# Peripherals.net
KiCad netlist of a schematic drawn in Altium Designer
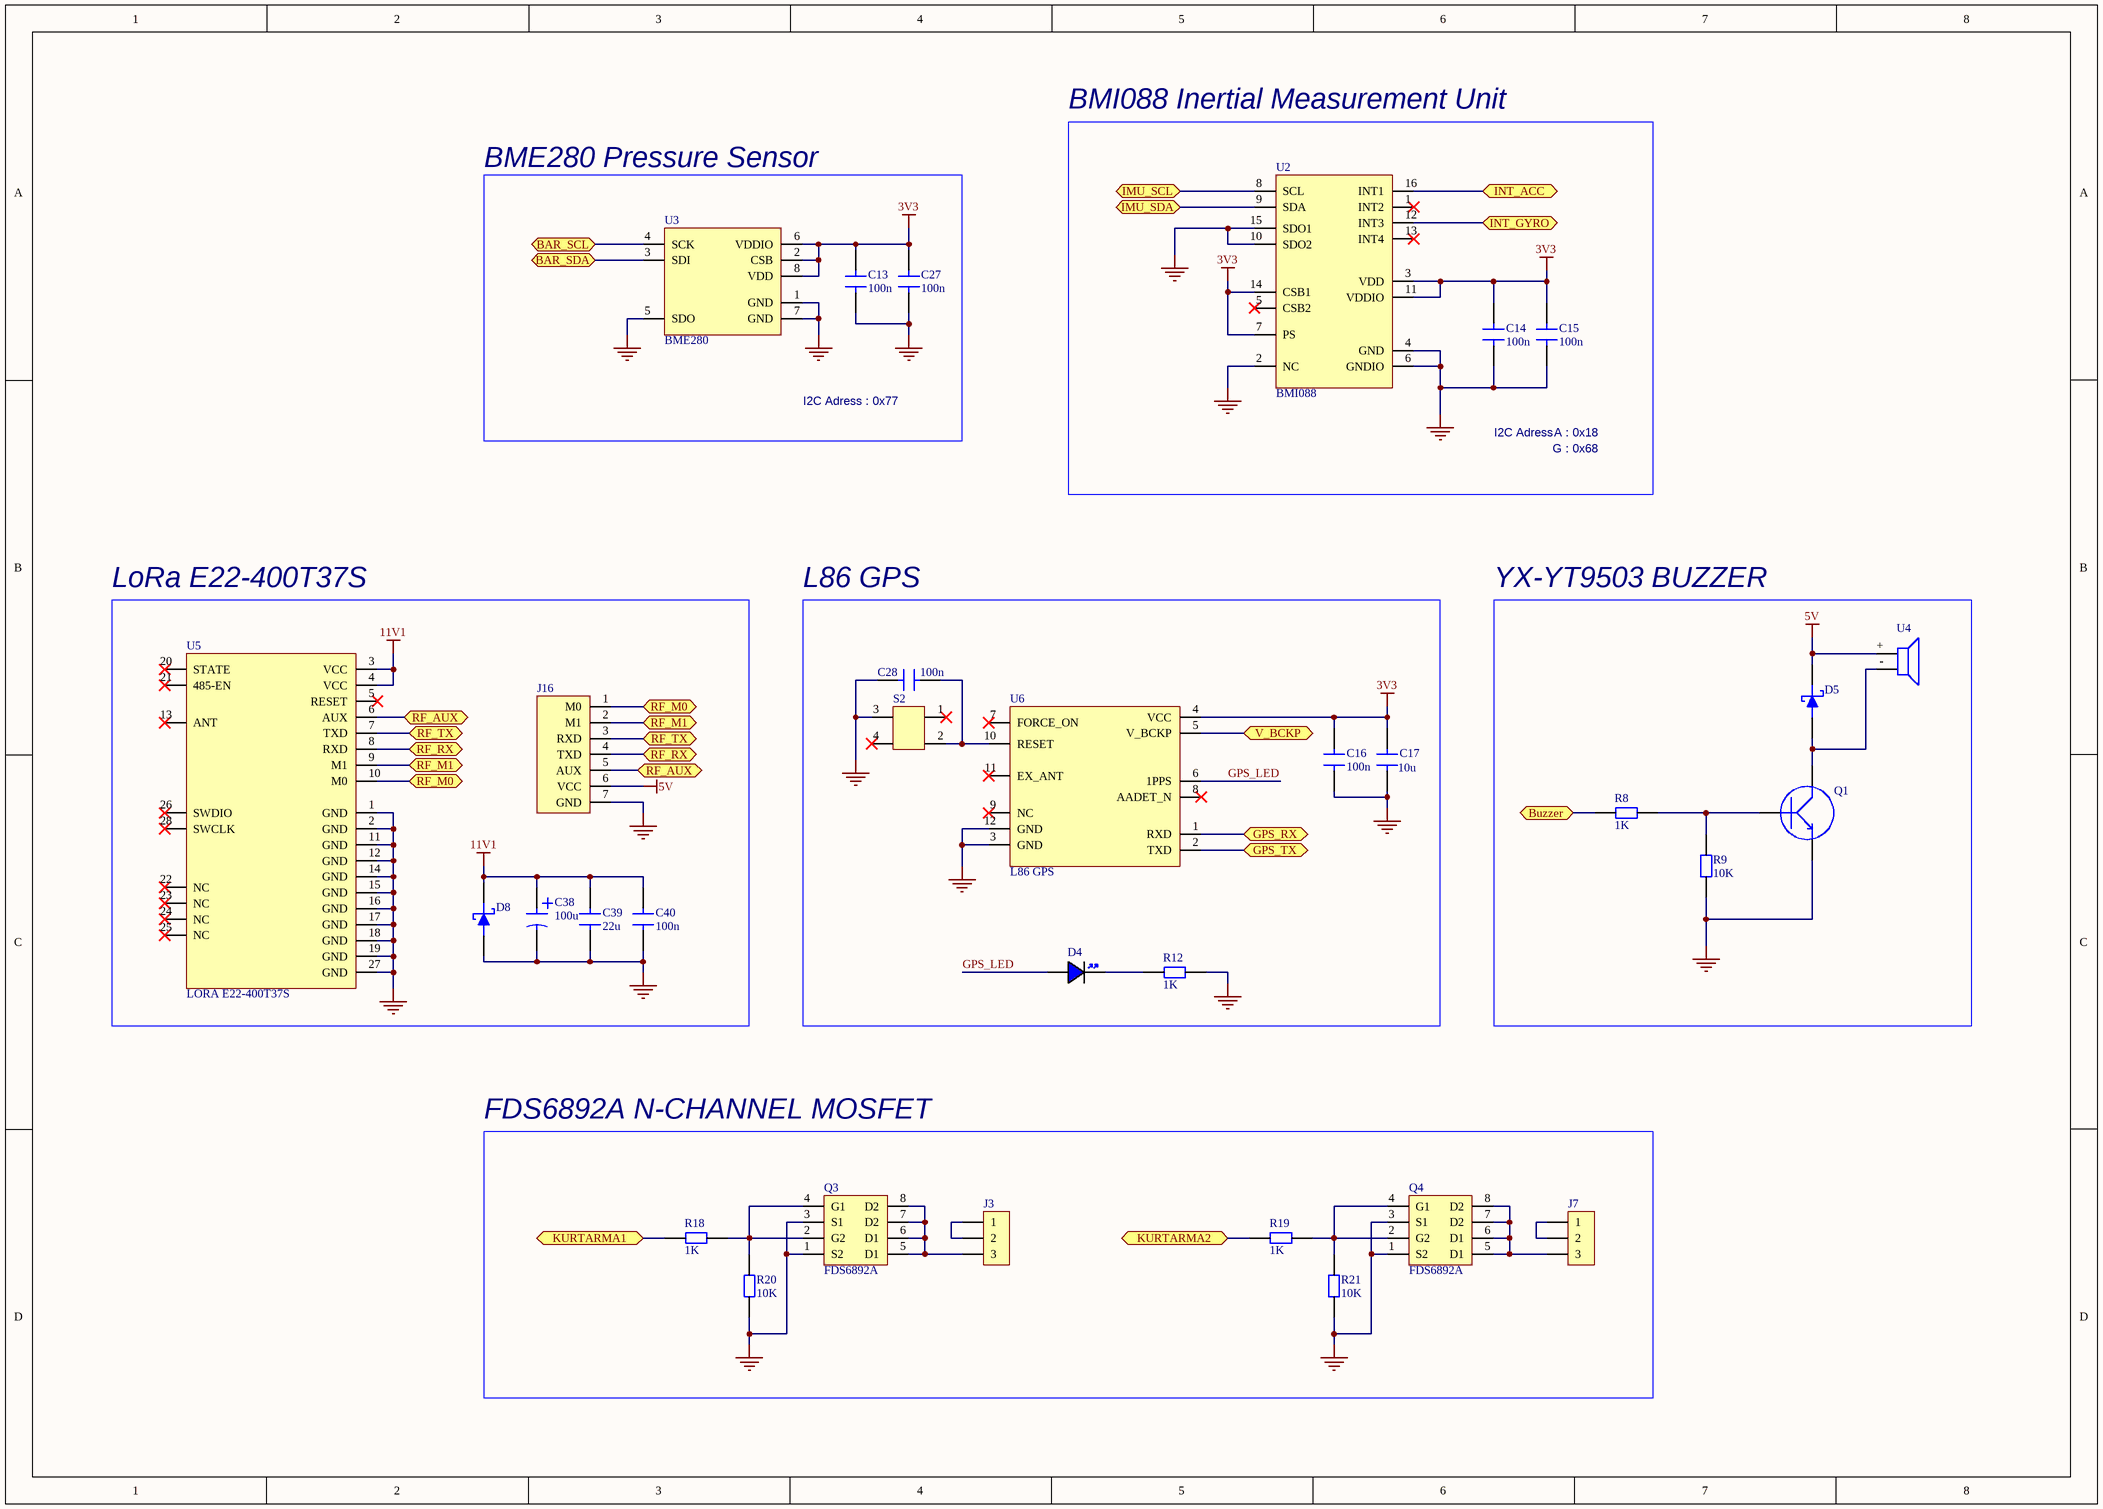
[diagram p0: Peripherals.SchDoc]

(export (version "E")
  (design (tool "Eeschema 10.0.6"))
  (components
    (comp (ref "C13")
      (value "100n")
      (footprint "CAP 0603")
      (description "Capacitor SMD 0603 50V")
      (libsource (lib "Schlib") (part "CAP 0603 50V"))
    )
    (comp (ref "C14")
      (value "100n")
      (footprint "CAP 0603")
      (description "Capacitor SMD 0603 50V")
      (libsource (lib "Schlib") (part "CAP 0603 50V"))
    )
    (comp (ref "C15")
      (value "100n")
      (footprint "CAP 0603")
      (description "Capacitor SMD 0603 50V")
      (libsource (lib "Schlib") (part "CAP 0603 50V"))
    )
    (comp (ref "C16")
      (value "100n")
      (footprint "CAP 0603")
      (description "Capacitor SMD 0603 50V")
      (libsource (lib "Schlib") (part "CAP 0603 50V"))
    )
    (comp (ref "C17")
      (value "10u")
      (footprint "CAP 0805")
      (description "Capacitor SMD 0805 25V")
      (libsource (lib "Schlib") (part "CAP 0805 25V"))
    )
    (comp (ref "C27")
      (value "100n")
      (footprint "CAP 0603")
      (description "Capacitor SMD 0603 50V")
      (libsource (lib "Schlib") (part "CAP 0603 50V"))
    )
    (comp (ref "C28")
      (value "100n")
      (footprint "CAP 0603")
      (description "Capacitor SMD 0603 50V")
      (libsource (lib "Schlib") (part "CAP 0603 50V"))
    )
    (comp (ref "C38")
      (value "100u")
      (footprint "865060653010")
      (fields
        (field (name "MANUFACTURER") "Wurth Electronics")
        (field (name "MANUFACTURER PART NUMBER") "865060653010")
      )
      (libsource (lib "Schlib") (part "865060653010"))
    )
    (comp (ref "C39")
      (value "22u")
      (footprint "CAP 1210")
      (description "Capacitor SMD 1210 25V")
      (libsource (lib "Schlib") (part "CAP 1210 25V"))
    )
    (comp (ref "C40")
      (value "100n")
      (footprint "CAP 0805")
      (description "Capacitor SMD 0805 50V")
      (libsource (lib "Schlib") (part "CAP 0805 50V"))
    )
    (comp (ref "D4")
      (value "LED 0805 BLUE")
      (footprint "LED 0805 BLUE")
      (description "LED 0805 GREEN SMD")
      (libsource (lib "Schlib") (part "LED 0805 BLUE"))
    )
    (comp (ref "D5")
      (value "TMBAT49FILM")
      (footprint "TMBAT49FILM")
      (description "Rectifier Diode Small Signal Schottky Si 80V 0.5A 2-Pin MELF T/R")
      (fields (field (name "MANUFACTURER") "STMicroelectronics"))
      (libsource (lib "Schlib") (part "TMBAT49FILM"))
    )
    (comp (ref "D8")
      (value "SMBJ14CA")
      (footprint "SMBJ12CA-13-F")
      (description "TVS DIODE 14VWM 23.2VC DO214AA")
      (fields (field (name "MANUFACTURER") "Littelfuse") (field (name "VOLTAGE") "14V"))
      (libsource (lib "Schlib") (part "SMBJ14CA"))
    )
    (comp (ref "J3")
      (value "JST B3B-XH-A")
      (footprint "JST_B3B-XH-A")
      (description "Connector Header, XH Series, 3 Position, 2.50mm, Through Hole, Press-Fit, Solder, Natural")
      (fields
        (field (name "MANUFACTURER") "JST")
        (field (name "MANUFACTURER PART NUMBER") "B3B-XH-A(LF)(SN)")
      )
      (libsource (lib "Schlib") (part "JST B3B-XH-A"))
    )
    (comp (ref "J7")
      (value "JST B3B-XH-A")
      (footprint "JST_B3B-XH-A")
      (description "Connector Header, XH Series, 3 Position, 2.50mm, Through Hole, Press-Fit, Solder, Natural")
      (fields
        (field (name "MANUFACTURER") "JST")
        (field (name "MANUFACTURER PART NUMBER") "B3B-XH-A(LF)(SN)")
      )
      (libsource (lib "Schlib") (part "JST B3B-XH-A"))
    )
    (comp (ref "J16")
      (value "LoRa E22-433T30D H")
      (footprint "LoRa E22-433T30D H")
      (description "E220-400T30D LoRa Module Header")
      (libsource (lib "Schlib") (part "LoRa E22-433T30D H"))
    )
    (comp (ref "Q1")
      (value "BC817-25W,115")
      (footprint "BC817-25")
      (description "BC817 Series 45 V 500 mA NPN General Purpose Transistor - SOT-23")
      (fields (field (name "MANUFACTURER") "Nexperia"))
      (libsource (lib "Schlib") (part "BC817-25W,115"))
    )
    (comp (ref "Q3")
      (value "FDS6892A")
      (footprint "DMG4822SSD-13")
      (description "Dual N-Channel Logic Level PWM Optimized PowerTrench® MOSFET 20V, 7.5A, 18mΩ")
      (fields (field (name "MANUFACTURER") "ON Semiconductor / Fairchild"))
      (libsource (lib "Schlib") (part "FDS6892A"))
    )
    (comp (ref "Q4")
      (value "FDS6892A")
      (footprint "DMG4822SSD-13")
      (description "Dual N-Channel Logic Level PWM Optimized PowerTrench® MOSFET 20V, 7.5A, 18mΩ")
      (fields (field (name "MANUFACTURER") "ON Semiconductor / Fairchild"))
      (libsource (lib "Schlib") (part "FDS6892A"))
    )
    (comp (ref "R8")
      (value "1K")
      (footprint "RES 0603")
      (description "Resistor SMD 0603")
      (libsource (lib "Schlib") (part "RES 0603"))
    )
    (comp (ref "R9")
      (value "10K")
      (footprint "RES 0603")
      (description "Resistor SMD 0603")
      (libsource (lib "Schlib") (part "RES 0603"))
    )
    (comp (ref "R12")
      (value "1K")
      (footprint "RES 0603")
      (description "Resistor SMD 0603")
      (libsource (lib "Schlib") (part "RES 0603"))
    )
    (comp (ref "R18")
      (value "1K")
      (footprint "RES 0805")
      (description "Resistor SMD 0805")
      (libsource (lib "Schlib") (part "RES 0805"))
    )
    (comp (ref "R19")
      (value "1K")
      (footprint "RES 0805")
      (description "Resistor SMD 0805")
      (libsource (lib "Schlib") (part "RES 0805"))
    )
    (comp (ref "R20")
      (value "10K")
      (footprint "RES 0805")
      (description "Resistor SMD 0805")
      (libsource (lib "Schlib") (part "RES 0805"))
    )
    (comp (ref "R21")
      (value "10K")
      (footprint "RES 0805")
      (description "Resistor SMD 0805")
      (libsource (lib "Schlib") (part "RES 0805"))
    )
    (comp (ref "S2")
      (value "FSM4JSMATR")
      (footprint "FSM4JSMATR")
      (description "Switch Tactile OFF (ON) SPST Round Button Gull Wing 0.05A 24VDC 1.57N SMD T/R")
      (fields (field (name "MANUFACTURER") "TE Connectivity Alcoswitch"))
      (libsource (lib "Schlib") (part "FSM4JSMATR"))
    )
    (comp (ref "U2")
      (value "BMI088")
      (footprint "BMI088")
      (description "BMI088 Series 3.6 V 6 Axis Digital Output Accelerometer Motion Sensor - LGA-16")
      (fields (field (name "MANUFACTURER") "Bosch Tools"))
      (libsource (lib "Schlib") (part "BMI088"))
    )
    (comp (ref "U3")
      (value "BME280")
      (footprint "BME280")
      (description "SENSOR PRESSURE HUMIDITY TEMP")
      (fields (field (name "MANUFACTURER") "Bosch"))
      (libsource (lib "Schlib") (part "BME280"))
    )
    (comp (ref "U4")
      (value "YX-YT9503")
      (footprint "YX-YT9503")
      (description "BUZZER MAGNETIC WITH CIRCUIT 3V 2.7-KHZ THT")
      (libsource (lib "Schlib") (part "YX-YT9503"))
    )
    (comp (ref "U5")
      (value "LORA E22-400T37S")
      (footprint "LORA E22-400T37S")
      (description "E22-400T37S LoRa Module")
      (libsource (lib "Schlib") (part "LORA E22-400T37S"))
    )
    (comp (ref "U6") (value "L86 GPS") (footprint "L86") (libsource (lib "Schlib") (part "L86 GPS")))
  )
  (nets
    (net (code "1") (name "/BAR_SCL") (class "Default")
      (node (ref "U3") (pin "4") (pinfunction "SCK_4") (pintype "passive"))
    )
    (net (code "2") (name "/BAR_SDA") (class "Default")
      (node (ref "U3") (pin "3") (pinfunction "SDI_3") (pintype "passive"))
    )
    (net (code "3") (name "/Buzzer") (class "Default")
      (node (ref "R8") (pin "1") (pinfunction "1_1") (pintype "passive"))
    )
    (net (code "4") (name "/GPS_LED") (class "Default")
      (node (ref "D4") (pin "A") (pinfunction "A_A") (pintype "passive"))
      (node (ref "U6") (pin "6") (pinfunction "1PPS_6") (pintype "passive"))
    )
    (net (code "5") (name "/GPS_RX") (class "Default")
      (node (ref "U6") (pin "1") (pinfunction "RXD_1") (pintype "passive"))
    )
    (net (code "6") (name "/GPS_TX") (class "Default")
      (node (ref "U6") (pin "2") (pinfunction "TXD_2") (pintype "passive"))
    )
    (net (code "7") (name "/IMU_SCL") (class "Default")
      (node (ref "U2") (pin "8") (pinfunction "SCL_8") (pintype "passive"))
    )
    (net (code "8") (name "/IMU_SDA") (class "Default")
      (node (ref "U2") (pin "9") (pinfunction "SDA_9") (pintype "passive"))
    )
    (net (code "9") (name "/INT_ACC") (class "Default")
      (node (ref "U2") (pin "16") (pinfunction "INT1_16") (pintype "passive"))
    )
    (net (code "10") (name "/INT_GYRO") (class "Default")
      (node (ref "U2") (pin "12") (pinfunction "INT3_12") (pintype "passive"))
    )
    (net (code "11") (name "/KURTARMA1") (class "Default")
      (node (ref "R18") (pin "1") (pinfunction "1_1") (pintype "passive"))
    )
    (net (code "12") (name "/KURTARMA2") (class "Default")
      (node (ref "R19") (pin "1") (pinfunction "1_1") (pintype "passive"))
    )
    (net (code "13") (name "/RF_AUX") (class "Default")
      (node (ref "J16") (pin "5") (pinfunction "AUX_5") (pintype "passive"))
      (node (ref "U5") (pin "6") (pinfunction "AUX_6") (pintype "passive"))
    )
    (net (code "14") (name "/RF_M0") (class "Default")
      (node (ref "J16") (pin "1") (pinfunction "M0_1") (pintype "passive"))
      (node (ref "U5") (pin "10") (pinfunction "M0_10") (pintype "passive"))
    )
    (net (code "15") (name "/RF_M1") (class "Default")
      (node (ref "J16") (pin "2") (pinfunction "M1_2") (pintype "passive"))
      (node (ref "U5") (pin "9") (pinfunction "M1_9") (pintype "passive"))
    )
    (net (code "16") (name "/RF_RX") (class "Default")
      (node (ref "J16") (pin "4") (pinfunction "TXD_4") (pintype "passive"))
      (node (ref "U5") (pin "8") (pinfunction "RXD_8") (pintype "passive"))
    )
    (net (code "17") (name "/RF_TX") (class "Default")
      (node (ref "J16") (pin "3") (pinfunction "RXD_3") (pintype "passive"))
      (node (ref "U5") (pin "7") (pinfunction "TXD_7") (pintype "passive"))
    )
    (net (code "18") (name "/V_BCKP") (class "Default")
      (node (ref "U6") (pin "5") (pinfunction "V_BCKP_5") (pintype "passive"))
    )
    (net (code "19") (name "3V3") (class "Default")
      (node (ref "C13") (pin "2") (pinfunction "2_2") (pintype "passive"))
      (node (ref "C14") (pin "2") (pinfunction "2_2") (pintype "passive"))
      (node (ref "C15") (pin "2") (pinfunction "2_2") (pintype "passive"))
      (node (ref "C16") (pin "2") (pinfunction "2_2") (pintype "passive"))
      (node (ref "C17") (pin "2") (pinfunction "2_2") (pintype "passive"))
      (node (ref "C27") (pin "2") (pinfunction "2_2") (pintype "passive"))
      (node (ref "U2") (pin "11") (pinfunction "VDDIO_11") (pintype "passive"))
      (node (ref "U2") (pin "14") (pinfunction "CSB1_14") (pintype "passive"))
      (node (ref "U2") (pin "3") (pinfunction "VDD_3") (pintype "passive"))
      (node (ref "U2") (pin "7") (pinfunction "PS_7") (pintype "passive"))
      (node (ref "U3") (pin "2") (pinfunction "CSB_2") (pintype "passive"))
      (node (ref "U3") (pin "6") (pinfunction "VDDIO_6") (pintype "passive"))
      (node (ref "U3") (pin "8") (pinfunction "VDD_8") (pintype "passive"))
      (node (ref "U6") (pin "4") (pinfunction "VCC_4") (pintype "passive"))
    )
    (net (code "20") (name "5V") (class "Default")
      (node (ref "D5") (pin "1") (pintype "passive"))
      (node (ref "J16") (pin "6") (pinfunction "VCC_6") (pintype "passive"))
      (node (ref "U4") (pin "+") (pinfunction "+_+") (pintype "passive"))
    )
    (net (code "21") (name "11V1") (class "Default")
      (node (ref "C38") (pin "1") (pinfunction "P_1") (pintype "passive"))
      (node (ref "C39") (pin "2") (pinfunction "2_2") (pintype "passive"))
      (node (ref "C40") (pin "2") (pinfunction "2_2") (pintype "passive"))
      (node (ref "D8") (pin "2") (pintype "passive"))
      (node (ref "U5") (pin "3") (pinfunction "VCC_3") (pintype "passive"))
      (node (ref "U5") (pin "4") (pinfunction "VCC_4") (pintype "passive"))
    )
    (net (code "22") (name "GND") (class "Default")
      (node (ref "C13") (pin "1") (pinfunction "1_1") (pintype "passive"))
      (node (ref "C14") (pin "1") (pinfunction "1_1") (pintype "passive"))
      (node (ref "C15") (pin "1") (pinfunction "1_1") (pintype "passive"))
      (node (ref "C16") (pin "1") (pinfunction "1_1") (pintype "passive"))
      (node (ref "C17") (pin "1") (pinfunction "1_1") (pintype "passive"))
      (node (ref "C27") (pin "1") (pinfunction "1_1") (pintype "passive"))
      (node (ref "C28") (pin "1") (pinfunction "1_1") (pintype "passive"))
      (node (ref "C38") (pin "2") (pinfunction "N_2") (pintype "passive"))
      (node (ref "C39") (pin "1") (pinfunction "1_1") (pintype "passive"))
      (node (ref "C40") (pin "1") (pinfunction "1_1") (pintype "passive"))
      (node (ref "D8") (pin "1") (pintype "passive"))
      (node (ref "J16") (pin "7") (pinfunction "GND_7") (pintype "passive"))
      (node (ref "Q1") (pin "2") (pinfunction "E_2") (pintype "passive"))
      (node (ref "Q3") (pin "1") (pinfunction "S2_1") (pintype "passive"))
      (node (ref "Q3") (pin "3") (pinfunction "S1_3") (pintype "passive"))
      (node (ref "Q4") (pin "1") (pinfunction "S2_1") (pintype "passive"))
      (node (ref "Q4") (pin "3") (pinfunction "S1_3") (pintype "passive"))
      (node (ref "R12") (pin "2") (pinfunction "2_2") (pintype "passive"))
      (node (ref "R20") (pin "1") (pinfunction "1_1") (pintype "passive"))
      (node (ref "R21") (pin "1") (pinfunction "1_1") (pintype "passive"))
      (node (ref "R9") (pin "1") (pinfunction "1_1") (pintype "passive"))
      (node (ref "S2") (pin "3") (pinfunction "3_3") (pintype "passive"))
      (node (ref "U2") (pin "10") (pinfunction "SDO2_10") (pintype "passive"))
      (node (ref "U2") (pin "15") (pinfunction "SDO1_15") (pintype "passive"))
      (node (ref "U2") (pin "2") (pinfunction "NC_2") (pintype "passive"))
      (node (ref "U2") (pin "4") (pinfunction "GND_4") (pintype "passive"))
      (node (ref "U2") (pin "6") (pinfunction "GNDIO_6") (pintype "passive"))
      (node (ref "U3") (pin "1") (pinfunction "GND_1") (pintype "passive"))
      (node (ref "U3") (pin "5") (pinfunction "SDO_5") (pintype "passive"))
      (node (ref "U3") (pin "7") (pinfunction "GND_7") (pintype "passive"))
      (node (ref "U5") (pin "1") (pinfunction "GND_1") (pintype "passive"))
      (node (ref "U5") (pin "11") (pinfunction "GND_11") (pintype "passive"))
      (node (ref "U5") (pin "12") (pinfunction "GND_12") (pintype "passive"))
      (node (ref "U5") (pin "14") (pinfunction "GND_14") (pintype "passive"))
      (node (ref "U5") (pin "15") (pinfunction "GND_15") (pintype "passive"))
      (node (ref "U5") (pin "16") (pinfunction "GND_16") (pintype "passive"))
      (node (ref "U5") (pin "17") (pinfunction "GND_17") (pintype "passive"))
      (node (ref "U5") (pin "18") (pinfunction "GND_18") (pintype "passive"))
      (node (ref "U5") (pin "19") (pinfunction "GND_19") (pintype "passive"))
      (node (ref "U5") (pin "2") (pinfunction "GND_2") (pintype "passive"))
      (node (ref "U5") (pin "27") (pinfunction "GND_27") (pintype "passive"))
      (node (ref "U6") (pin "12") (pinfunction "GND_12") (pintype "passive"))
      (node (ref "U6") (pin "3") (pinfunction "GND_3") (pintype "passive"))
    )
    (net (code "23") (name "Net-(D4-PadK)") (class "Default")
      (node (ref "D4") (pin "K") (pinfunction "K_K") (pintype "passive"))
      (node (ref "R12") (pin "1") (pinfunction "1_1") (pintype "passive"))
    )
    (net (code "24") (name "Net-(J3-Pad1)") (class "Default")
      (node (ref "J3") (pin "1") (pinfunction "1_1") (pintype "passive"))
      (node (ref "J3") (pin "2") (pinfunction "2_2") (pintype "passive"))
    )
    (net (code "25") (name "Net-(J3-Pad3)") (class "Default")
      (node (ref "J3") (pin "3") (pinfunction "3_3") (pintype "passive"))
      (node (ref "Q3") (pin "5") (pinfunction "D1_5") (pintype "passive"))
      (node (ref "Q3") (pin "6") (pinfunction "D1_6") (pintype "passive"))
      (node (ref "Q3") (pin "7") (pinfunction "D2_7") (pintype "passive"))
      (node (ref "Q3") (pin "8") (pinfunction "D2_8") (pintype "passive"))
    )
    (net (code "26") (name "Net-(J7-Pad1)") (class "Default")
      (node (ref "J7") (pin "1") (pinfunction "1_1") (pintype "passive"))
      (node (ref "J7") (pin "2") (pinfunction "2_2") (pintype "passive"))
    )
    (net (code "27") (name "Net-(J7-Pad3)") (class "Default")
      (node (ref "J7") (pin "3") (pinfunction "3_3") (pintype "passive"))
      (node (ref "Q4") (pin "5") (pinfunction "D1_5") (pintype "passive"))
      (node (ref "Q4") (pin "6") (pinfunction "D1_6") (pintype "passive"))
      (node (ref "Q4") (pin "7") (pinfunction "D2_7") (pintype "passive"))
      (node (ref "Q4") (pin "8") (pinfunction "D2_8") (pintype "passive"))
    )
    (net (code "28") (name "Net-(Q1-B)") (class "Default")
      (node (ref "Q1") (pin "1") (pinfunction "B_1") (pintype "passive"))
      (node (ref "R8") (pin "2") (pinfunction "2_2") (pintype "passive"))
      (node (ref "R9") (pin "2") (pinfunction "2_2") (pintype "passive"))
    )
    (net (code "29") (name "Net-(Q1-C)") (class "Default")
      (node (ref "D5") (pin "2") (pintype "passive"))
      (node (ref "Q1") (pin "3") (pinfunction "C_3") (pintype "passive"))
      (node (ref "U4") (pin "-") (pinfunction "-_-") (pintype "passive"))
    )
    (net (code "30") (name "Net-(Q3-G1)") (class "Default")
      (node (ref "Q3") (pin "2") (pinfunction "G2_2") (pintype "passive"))
      (node (ref "Q3") (pin "4") (pinfunction "G1_4") (pintype "passive"))
      (node (ref "R18") (pin "2") (pinfunction "2_2") (pintype "passive"))
      (node (ref "R20") (pin "2") (pinfunction "2_2") (pintype "passive"))
    )
    (net (code "31") (name "Net-(Q4-G1)") (class "Default")
      (node (ref "Q4") (pin "2") (pinfunction "G2_2") (pintype "passive"))
      (node (ref "Q4") (pin "4") (pinfunction "G1_4") (pintype "passive"))
      (node (ref "R19") (pin "2") (pinfunction "2_2") (pintype "passive"))
      (node (ref "R21") (pin "2") (pinfunction "2_2") (pintype "passive"))
    )
    (net (code "32") (name "Net-(U6-RESET)") (class "Default")
      (node (ref "C28") (pin "2") (pinfunction "2_2") (pintype "passive"))
      (node (ref "S2") (pin "2") (pinfunction "2_2") (pintype "passive"))
      (node (ref "U6") (pin "10") (pinfunction "RESET_10") (pintype "passive"))
    )
    (net (code "33") (name "unconnected-(S2-Pad1)") (class "Default")
      (node (ref "S2") (pin "1") (pinfunction "1_1") (pintype "passive+no_connect"))
    )
    (net (code "34") (name "unconnected-(S2-Pad4)") (class "Default")
      (node (ref "S2") (pin "4") (pinfunction "4_4") (pintype "passive+no_connect"))
    )
    (net (code "35") (name "unconnected-(U2-CSB2-Pad5)") (class "Default")
      (node (ref "U2") (pin "5") (pinfunction "CSB2_5") (pintype "passive+no_connect"))
    )
    (net (code "36") (name "unconnected-(U2-INT2-Pad1)") (class "Default")
      (node (ref "U2") (pin "1") (pinfunction "INT2_1") (pintype "passive+no_connect"))
    )
    (net (code "37") (name "unconnected-(U2-INT4-Pad13)") (class "Default")
      (node (ref "U2") (pin "13") (pinfunction "INT4_13") (pintype "passive+no_connect"))
    )
    (net (code "38") (name "unconnected-(U5-485-EN-Pad21)") (class "Default")
      (node (ref "U5") (pin "21") (pinfunction "485-EN_21") (pintype "passive+no_connect"))
    )
    (net (code "39") (name "unconnected-(U5-ANT-Pad13)") (class "Default")
      (node (ref "U5") (pin "13") (pinfunction "ANT_13") (pintype "passive+no_connect"))
    )
    (net (code "40") (name "unconnected-(U5-NC-Pad22)") (class "Default")
      (node (ref "U5") (pin "22") (pinfunction "NC_22") (pintype "passive+no_connect"))
    )
    (net (code "41") (name "unconnected-(U5-NC-Pad23)") (class "Default")
      (node (ref "U5") (pin "23") (pinfunction "NC_23") (pintype "passive+no_connect"))
    )
    (net (code "42") (name "unconnected-(U5-NC-Pad24)") (class "Default")
      (node (ref "U5") (pin "24") (pinfunction "NC_24") (pintype "passive+no_connect"))
    )
    (net (code "43") (name "unconnected-(U5-NC-Pad25)") (class "Default")
      (node (ref "U5") (pin "25") (pinfunction "NC_25") (pintype "passive+no_connect"))
    )
    (net (code "44") (name "unconnected-(U5-RESET-Pad5)") (class "Default")
      (node (ref "U5") (pin "5") (pinfunction "RESET_5") (pintype "passive+no_connect"))
    )
    (net (code "45") (name "unconnected-(U5-STATE-Pad20)") (class "Default")
      (node (ref "U5") (pin "20") (pinfunction "STATE_20") (pintype "passive+no_connect"))
    )
    (net (code "46") (name "unconnected-(U5-SWCLK-Pad28)") (class "Default")
      (node (ref "U5") (pin "28") (pinfunction "SWCLK_28") (pintype "passive+no_connect"))
    )
    (net (code "47") (name "unconnected-(U5-SWDIO-Pad26)") (class "Default")
      (node (ref "U5") (pin "26") (pinfunction "SWDIO_26") (pintype "passive+no_connect"))
    )
    (net (code "48") (name "unconnected-(U6-AADET_N-Pad8)") (class "Default")
      (node (ref "U6") (pin "8") (pinfunction "AADET_N_8") (pintype "passive+no_connect"))
    )
    (net (code "49") (name "unconnected-(U6-EX_ANT-Pad11)") (class "Default")
      (node (ref "U6") (pin "11") (pinfunction "EX_ANT_11") (pintype "passive+no_connect"))
    )
    (net (code "50") (name "unconnected-(U6-FORCE_ON-Pad7)") (class "Default")
      (node (ref "U6") (pin "7") (pinfunction "FORCE_ON_7") (pintype "passive+no_connect"))
    )
    (net (code "51") (name "unconnected-(U6-NC-Pad9)") (class "Default")
      (node (ref "U6") (pin "9") (pinfunction "NC_9") (pintype "passive+no_connect"))
    )
  )
)
